# arduboy-progger.net
KiCad netlist of a schematic drawn in EAGLE
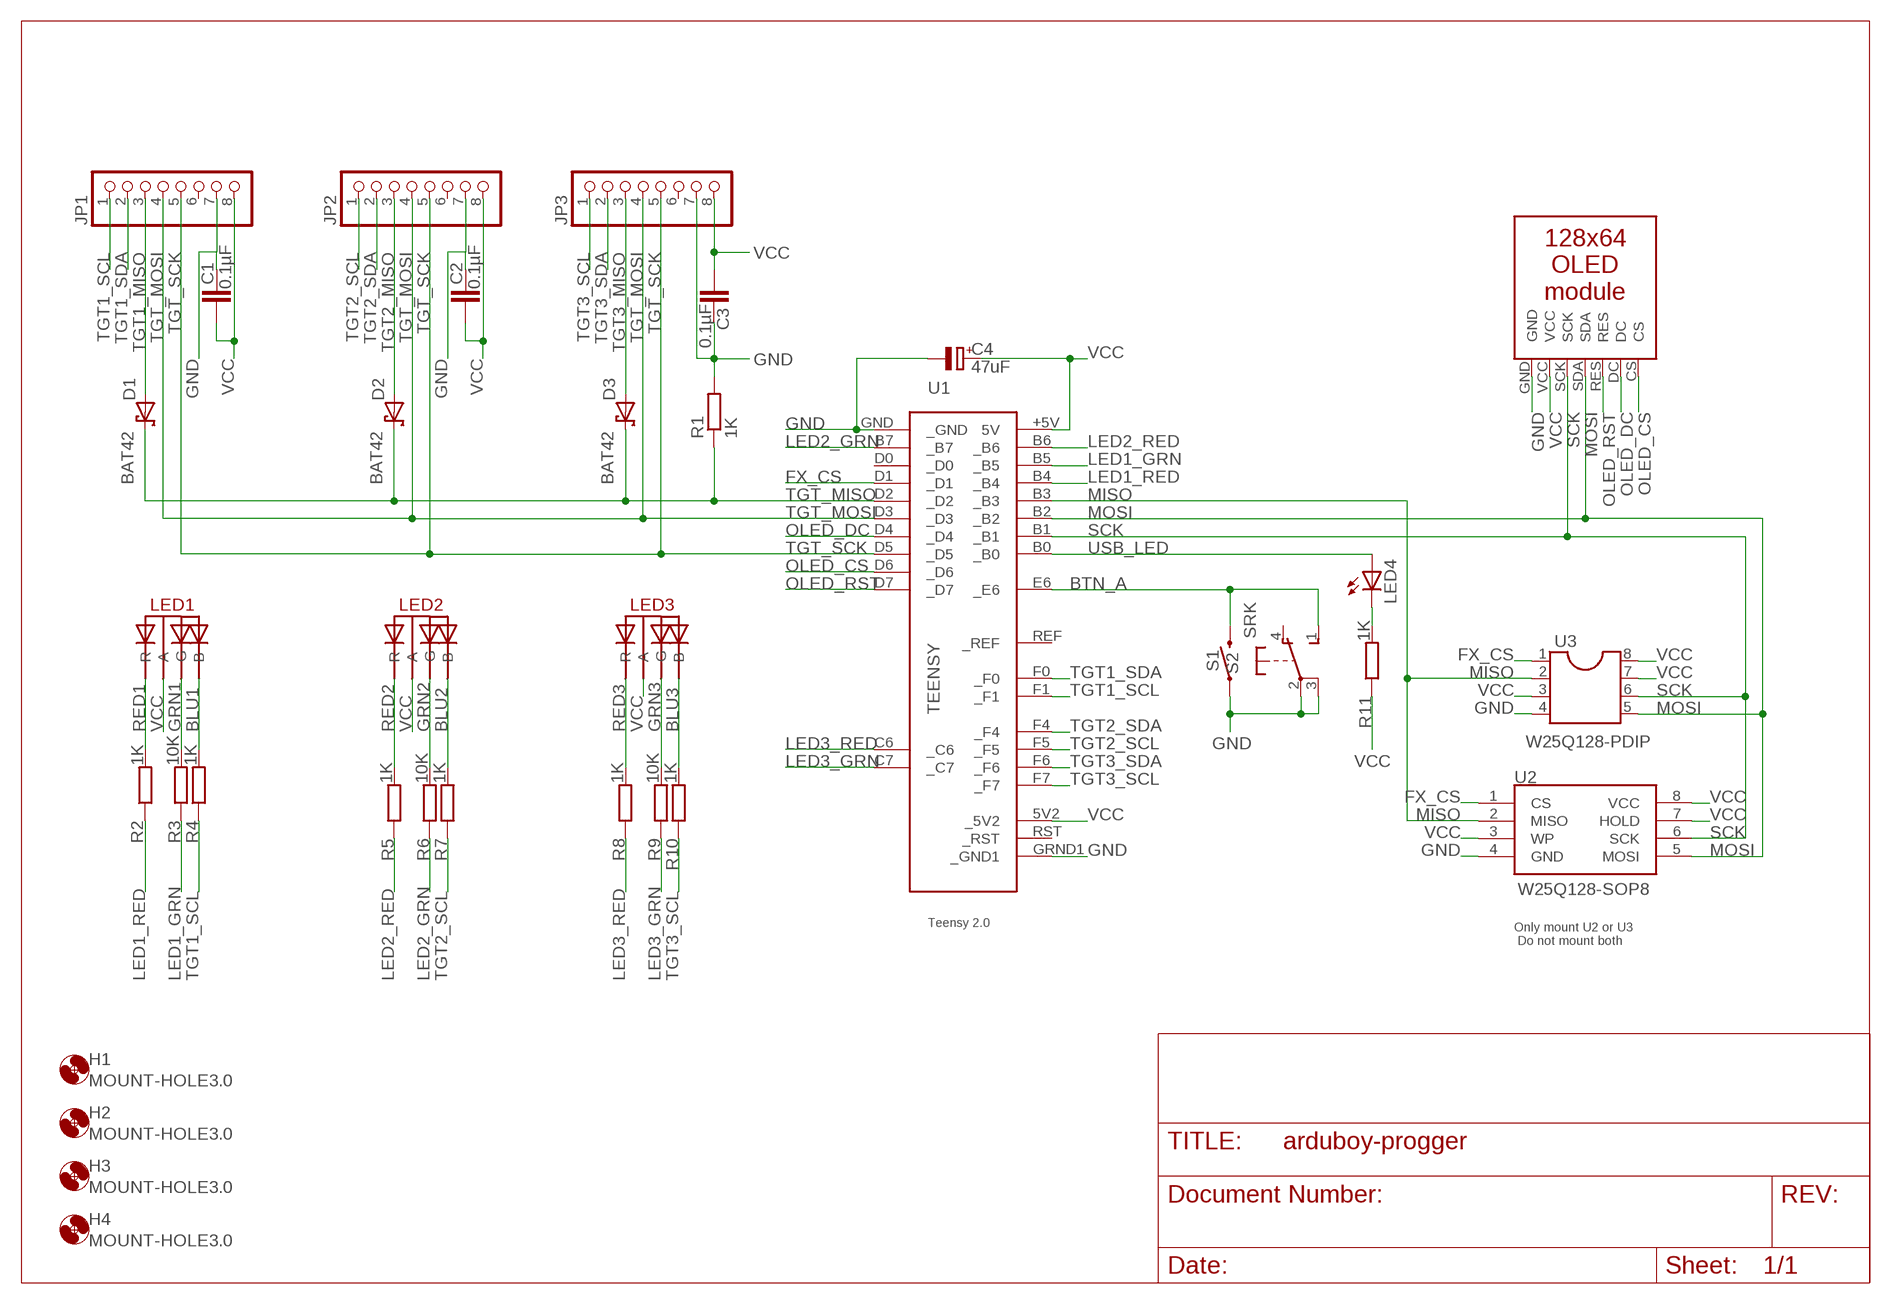
[diagram p0: schematic, sheet 1]

(export (version "E")
  (design (tool "Eeschema 10.0.6"))
  (components
    (comp (ref "C1")
      (value "0.1µF")
      (footprint "eagle-import:C025-025X050")
      (libsource (lib "eagle-import") (part "C-EU025-025X050"))
    )
    (comp (ref "C2")
      (value "0.1µF")
      (footprint "eagle-import:C025-025X050")
      (libsource (lib "eagle-import") (part "C-EU025-025X050"))
    )
    (comp (ref "C3")
      (value "0.1µF")
      (footprint "eagle-import:C025-025X050")
      (libsource (lib "eagle-import") (part "C-EU025-025X050"))
    )
    (comp (ref "C4")
      (value "47uF")
      (footprint "eagle-import:E2,5-6")
      (libsource (lib "eagle-import") (part "CPOL-EUE2.5-6"))
    )
    (comp (ref "D1")
      (value "BAT42")
      (footprint "eagle-import:DO35-10")
      (libsource (lib "eagle-import") (part "BAT42"))
    )
    (comp (ref "D2")
      (value "BAT42")
      (footprint "eagle-import:DO35-10")
      (libsource (lib "eagle-import") (part "BAT42"))
    )
    (comp (ref "D3")
      (value "BAT42")
      (footprint "eagle-import:DO35-10")
      (libsource (lib "eagle-import") (part "BAT42"))
    )
    (comp (ref "H1")
      (value "MOUNT-HOLE3.0")
      (footprint "eagle-import:3,0")
      (libsource (lib "eagle-import") (part "MOUNT-HOLE3.0"))
    )
    (comp (ref "H2")
      (value "MOUNT-HOLE3.0")
      (footprint "eagle-import:3,0")
      (libsource (lib "eagle-import") (part "MOUNT-HOLE3.0"))
    )
    (comp (ref "H3")
      (value "MOUNT-HOLE3.0")
      (footprint "eagle-import:3,0")
      (libsource (lib "eagle-import") (part "MOUNT-HOLE3.0"))
    )
    (comp (ref "H4")
      (value "MOUNT-HOLE3.0")
      (footprint "eagle-import:3,0")
      (libsource (lib "eagle-import") (part "MOUNT-HOLE3.0"))
    )
    (comp (ref "JP1")
      (value "PINHD-1X8")
      (footprint "eagle-import:1X08")
      (libsource (lib "eagle-import") (part "PINHD-1X8"))
    )
    (comp (ref "JP2")
      (value "PINHD-1X8")
      (footprint "eagle-import:1X08")
      (libsource (lib "eagle-import") (part "PINHD-1X8"))
    )
    (comp (ref "JP3")
      (value "PINHD-1X8")
      (footprint "eagle-import:1X08")
      (libsource (lib "eagle-import") (part "PINHD-1X8"))
    )
    (comp (ref "LED1")
      (value "5MMRGBLED-CA")
      (footprint "eagle-import:LED5MMRGB")
      (libsource (lib "eagle-import") (part "5MMRGBLED-CA"))
    )
    (comp (ref "LED2")
      (value "5MMRGBLED-CA")
      (footprint "eagle-import:LED5MMRGB")
      (libsource (lib "eagle-import") (part "5MMRGBLED-CA"))
    )
    (comp (ref "LED3")
      (value "5MMRGBLED-CA")
      (footprint "eagle-import:LED5MMRGB")
      (libsource (lib "eagle-import") (part "5MMRGBLED-CA"))
    )
    (comp (ref "LED4")
      (value "LED5MM")
      (footprint "eagle-import:LED5MM")
      (libsource (lib "eagle-import") (part "LED5MM"))
    )
    (comp (ref "OLED1")
      (value "OLED")
      (footprint "eagle-import:OLED")
      (libsource (lib "eagle-import") (part "OLED"))
    )
    (comp (ref "R1")
      (value "1K")
      (footprint "eagle-import:0207_10")
      (libsource (lib "eagle-import") (part "R-EU_0207/10"))
    )
    (comp (ref "R2")
      (value "1K")
      (footprint "eagle-import:0207_10")
      (libsource (lib "eagle-import") (part "R-EU_0207/10"))
    )
    (comp (ref "R3")
      (value "10K")
      (footprint "eagle-import:0207_10")
      (libsource (lib "eagle-import") (part "R-EU_0207/10"))
    )
    (comp (ref "R4")
      (value "1K")
      (footprint "eagle-import:0207_10")
      (libsource (lib "eagle-import") (part "R-EU_0207/10"))
    )
    (comp (ref "R5")
      (value "1K")
      (footprint "eagle-import:0207_10")
      (libsource (lib "eagle-import") (part "R-EU_0207/10"))
    )
    (comp (ref "R6")
      (value "10K")
      (footprint "eagle-import:0207_10")
      (libsource (lib "eagle-import") (part "R-EU_0207/10"))
    )
    (comp (ref "R7")
      (value "1K")
      (footprint "eagle-import:0207_10")
      (libsource (lib "eagle-import") (part "R-EU_0207/10"))
    )
    (comp (ref "R8")
      (value "1K")
      (footprint "eagle-import:0207_10")
      (libsource (lib "eagle-import") (part "R-EU_0207/10"))
    )
    (comp (ref "R9")
      (value "10K")
      (footprint "eagle-import:0207_10")
      (libsource (lib "eagle-import") (part "R-EU_0207/10"))
    )
    (comp (ref "R10")
      (value "1K")
      (footprint "eagle-import:0207_10")
      (libsource (lib "eagle-import") (part "R-EU_0207/10"))
    )
    (comp (ref "R11")
      (value "1K")
      (footprint "eagle-import:0207_10")
      (libsource (lib "eagle-import") (part "R-EU_0207/10"))
    )
    (comp (ref "S1")
      (value "MOMENTARY-SWITCH-SPST-PTH-6.0MM")
      (footprint "eagle-import:TACTILE_SWITCH_PTH_6.0MM")
      (libsource (lib "eagle-import") (part "MOMENTARY-SWITCH-SPST-PTH-6.0MM"))
    )
    (comp (ref "S2")
      (value "SRK")
      (footprint "eagle-import:SRK")
      (libsource (lib "eagle-import") (part "SRK"))
    )
    (comp (ref "U1")
      (value "TEENSY")
      (footprint "eagle-import:TEENSY")
      (libsource (lib "eagle-import") (part "TEENSY"))
    )
    (comp (ref "U2")
      (value "W25Q128-SOP8")
      (footprint "eagle-import:SO08-EIAJ")
      (libsource (lib "eagle-import") (part "SPI_FLASH-X25XXSMD1"))
    )
    (comp (ref "U3")
      (value "W25Q128-PDIP")
      (footprint "eagle-import:SOCKET-08")
      (libsource (lib "eagle-import") (part "DIL8S"))
    )
  )
  (nets
    (net (code "1") (name "/BLU1") (class "Default")
      (node (ref "LED1") (pin "B$1") (pinfunction "B_B$1") (pintype "bidirectional"))
      (node (ref "R4") (pin "2") (pinfunction "2_2") (pintype "passive"))
    )
    (net (code "2") (name "/BLU2") (class "Default")
      (node (ref "LED2") (pin "B$1") (pinfunction "B_B$1") (pintype "bidirectional"))
      (node (ref "R7") (pin "2") (pinfunction "2_2") (pintype "passive"))
    )
    (net (code "3") (name "/BLU3") (class "Default")
      (node (ref "LED3") (pin "B$1") (pinfunction "B_B$1") (pintype "bidirectional"))
      (node (ref "R10") (pin "2") (pinfunction "2_2") (pintype "passive"))
    )
    (net (code "4") (name "/BTN_A") (class "Default")
      (node (ref "S1") (pin "3") (pinfunction "2_3") (pintype "passive"))
      (node (ref "S2") (pin "1") (pinfunction "S_1") (pintype "passive"))
      (node (ref "U1") (pin "E6") (pinfunction "_E6_E6") (pintype "bidirectional"))
    )
    (net (code "5") (name "/FX_CS") (class "Default")
      (node (ref "U1") (pin "D1") (pinfunction "_D1_D1") (pintype "bidirectional"))
      (node (ref "U2") (pin "1") (pinfunction "CS_1") (pintype "bidirectional"))
      (node (ref "U3") (pin "1") (pinfunction "1_1") (pintype "passive"))
    )
    (net (code "6") (name "/GND") (class "Default")
      (node (ref "C1") (pin "1") (pinfunction "1_1") (pintype "passive"))
      (node (ref "C2") (pin "1") (pinfunction "1_1") (pintype "passive"))
      (node (ref "C3") (pin "1") (pinfunction "1_1") (pintype "passive"))
      (node (ref "C4") (pin "-") (pinfunction "-_-") (pintype "passive"))
      (node (ref "JP1") (pin "7") (pinfunction "7_7") (pintype "passive"))
      (node (ref "JP2") (pin "7") (pinfunction "7_7") (pintype "passive"))
      (node (ref "JP3") (pin "7") (pinfunction "7_7") (pintype "passive"))
      (node (ref "OLED1") (pin "GND") (pinfunction "GND_GND") (pintype "power_in"))
      (node (ref "R1") (pin "2") (pinfunction "2_2") (pintype "passive"))
      (node (ref "S1") (pin "1") (pinfunction "1_1") (pintype "passive"))
      (node (ref "S2") (pin "2") (pinfunction "P_2") (pintype "passive"))
      (node (ref "S2") (pin "3") (pinfunction "P_3") (pintype "passive"))
      (node (ref "U1") (pin "GND") (pinfunction "_GND_GND") (pintype "bidirectional"))
      (node (ref "U1") (pin "GRND1") (pinfunction "_GND1_GRND1") (pintype "bidirectional"))
      (node (ref "U2") (pin "4") (pinfunction "GND_4") (pintype "power_in"))
      (node (ref "U3") (pin "4") (pinfunction "4_4") (pintype "passive"))
    )
    (net (code "7") (name "/GRN1") (class "Default")
      (node (ref "LED1") (pin "G$1") (pinfunction "G_G$1") (pintype "bidirectional"))
      (node (ref "R3") (pin "2") (pinfunction "2_2") (pintype "passive"))
    )
    (net (code "8") (name "/GRN2") (class "Default")
      (node (ref "LED2") (pin "G$1") (pinfunction "G_G$1") (pintype "bidirectional"))
      (node (ref "R6") (pin "2") (pinfunction "2_2") (pintype "passive"))
    )
    (net (code "9") (name "/GRN3") (class "Default")
      (node (ref "LED3") (pin "G$1") (pinfunction "G_G$1") (pintype "bidirectional"))
      (node (ref "R9") (pin "2") (pinfunction "2_2") (pintype "passive"))
    )
    (net (code "10") (name "/LED1_GRN") (class "Default")
      (node (ref "R3") (pin "1") (pinfunction "1_1") (pintype "passive"))
      (node (ref "U1") (pin "B5") (pinfunction "_B5_B5") (pintype "bidirectional"))
    )
    (net (code "11") (name "/LED1_RED") (class "Default")
      (node (ref "R2") (pin "1") (pinfunction "1_1") (pintype "passive"))
      (node (ref "U1") (pin "B4") (pinfunction "_B4_B4") (pintype "bidirectional"))
    )
    (net (code "12") (name "/LED2_GRN") (class "Default")
      (node (ref "R6") (pin "1") (pinfunction "1_1") (pintype "passive"))
      (node (ref "U1") (pin "B7") (pinfunction "_B7_B7") (pintype "bidirectional"))
    )
    (net (code "13") (name "/LED2_RED") (class "Default")
      (node (ref "R5") (pin "1") (pinfunction "1_1") (pintype "passive"))
      (node (ref "U1") (pin "B6") (pinfunction "_B6_B6") (pintype "bidirectional"))
    )
    (net (code "14") (name "/LED3_GRN") (class "Default")
      (node (ref "R9") (pin "1") (pinfunction "1_1") (pintype "passive"))
      (node (ref "U1") (pin "C7") (pinfunction "_C7_C7") (pintype "bidirectional"))
    )
    (net (code "15") (name "/LED3_RED") (class "Default")
      (node (ref "R8") (pin "1") (pinfunction "1_1") (pintype "passive"))
      (node (ref "U1") (pin "C6") (pinfunction "_C6_C6") (pintype "bidirectional"))
    )
    (net (code "16") (name "/MISO") (class "Default")
      (node (ref "U1") (pin "B3") (pinfunction "_B3_B3") (pintype "bidirectional"))
      (node (ref "U2") (pin "2") (pinfunction "MISO_2") (pintype "bidirectional"))
      (node (ref "U3") (pin "2") (pinfunction "2_2") (pintype "passive"))
    )
    (net (code "17") (name "/MOSI") (class "Default")
      (node (ref "OLED1") (pin "SDA") (pinfunction "SDA_SDA") (pintype "input"))
      (node (ref "U1") (pin "B2") (pinfunction "_B2_B2") (pintype "bidirectional"))
      (node (ref "U2") (pin "5") (pinfunction "MOSI_5") (pintype "bidirectional"))
      (node (ref "U3") (pin "5") (pinfunction "5_5") (pintype "passive"))
    )
    (net (code "18") (name "/OLED_CS") (class "Default")
      (node (ref "OLED1") (pin "CS") (pinfunction "CS_CS") (pintype "input"))
      (node (ref "U1") (pin "D6") (pinfunction "_D6_D6") (pintype "bidirectional"))
    )
    (net (code "19") (name "/OLED_DC") (class "Default")
      (node (ref "OLED1") (pin "DC") (pinfunction "DC_DC") (pintype "input"))
      (node (ref "U1") (pin "D4") (pinfunction "_D4_D4") (pintype "bidirectional"))
    )
    (net (code "20") (name "/OLED_RST") (class "Default")
      (node (ref "OLED1") (pin "RES") (pinfunction "RES_RES") (pintype "input"))
      (node (ref "U1") (pin "D7") (pinfunction "_D7_D7") (pintype "bidirectional"))
    )
    (net (code "21") (name "/RED1") (class "Default")
      (node (ref "LED1") (pin "R$1") (pinfunction "R_R$1") (pintype "bidirectional"))
      (node (ref "R2") (pin "2") (pinfunction "2_2") (pintype "passive"))
    )
    (net (code "22") (name "/RED2") (class "Default")
      (node (ref "LED2") (pin "R$1") (pinfunction "R_R$1") (pintype "bidirectional"))
      (node (ref "R5") (pin "2") (pinfunction "2_2") (pintype "passive"))
    )
    (net (code "23") (name "/RED3") (class "Default")
      (node (ref "LED3") (pin "R$1") (pinfunction "R_R$1") (pintype "bidirectional"))
      (node (ref "R8") (pin "2") (pinfunction "2_2") (pintype "passive"))
    )
    (net (code "24") (name "/SCK") (class "Default")
      (node (ref "OLED1") (pin "SCK") (pinfunction "SCK_SCK") (pintype "input"))
      (node (ref "U1") (pin "B1") (pinfunction "_B1_B1") (pintype "bidirectional"))
      (node (ref "U2") (pin "6") (pinfunction "SCK_6") (pintype "bidirectional"))
      (node (ref "U3") (pin "6") (pinfunction "6_6") (pintype "passive"))
    )
    (net (code "25") (name "/TGT1_MISO") (class "Default")
      (node (ref "D1") (pin "A") (pinfunction "A_A") (pintype "passive"))
      (node (ref "JP1") (pin "3") (pinfunction "3_3") (pintype "passive"))
    )
    (net (code "26") (name "/TGT1_SCL") (class "Default")
      (node (ref "JP1") (pin "1") (pinfunction "1_1") (pintype "passive"))
      (node (ref "R4") (pin "1") (pinfunction "1_1") (pintype "passive"))
      (node (ref "U1") (pin "F1") (pinfunction "_F1_F1") (pintype "bidirectional"))
    )
    (net (code "27") (name "/TGT1_SDA") (class "Default")
      (node (ref "JP1") (pin "2") (pinfunction "2_2") (pintype "passive"))
      (node (ref "U1") (pin "F0") (pinfunction "_F0_F0") (pintype "bidirectional"))
    )
    (net (code "28") (name "/TGT2_MISO") (class "Default")
      (node (ref "D2") (pin "A") (pinfunction "A_A") (pintype "passive"))
      (node (ref "JP2") (pin "3") (pinfunction "3_3") (pintype "passive"))
    )
    (net (code "29") (name "/TGT2_SCL") (class "Default")
      (node (ref "JP2") (pin "1") (pinfunction "1_1") (pintype "passive"))
      (node (ref "R7") (pin "1") (pinfunction "1_1") (pintype "passive"))
      (node (ref "U1") (pin "F5") (pinfunction "_F5_F5") (pintype "bidirectional"))
    )
    (net (code "30") (name "/TGT2_SDA") (class "Default")
      (node (ref "JP2") (pin "2") (pinfunction "2_2") (pintype "passive"))
      (node (ref "U1") (pin "F4") (pinfunction "_F4_F4") (pintype "bidirectional"))
    )
    (net (code "31") (name "/TGT3_MISO") (class "Default")
      (node (ref "D3") (pin "A") (pinfunction "A_A") (pintype "passive"))
      (node (ref "JP3") (pin "3") (pinfunction "3_3") (pintype "passive"))
    )
    (net (code "32") (name "/TGT3_SCL") (class "Default")
      (node (ref "JP3") (pin "1") (pinfunction "1_1") (pintype "passive"))
      (node (ref "R10") (pin "1") (pinfunction "1_1") (pintype "passive"))
      (node (ref "U1") (pin "F7") (pinfunction "_F7_F7") (pintype "bidirectional"))
    )
    (net (code "33") (name "/TGT3_SDA") (class "Default")
      (node (ref "JP3") (pin "2") (pinfunction "2_2") (pintype "passive"))
      (node (ref "U1") (pin "F6") (pinfunction "_F6_F6") (pintype "bidirectional"))
    )
    (net (code "34") (name "/TGT_MISO") (class "Default")
      (node (ref "D1") (pin "C") (pinfunction "C_C") (pintype "passive"))
      (node (ref "D2") (pin "C") (pinfunction "C_C") (pintype "passive"))
      (node (ref "D3") (pin "C") (pinfunction "C_C") (pintype "passive"))
      (node (ref "R1") (pin "1") (pinfunction "1_1") (pintype "passive"))
      (node (ref "U1") (pin "D2") (pinfunction "_D2_D2") (pintype "bidirectional"))
    )
    (net (code "35") (name "/TGT_MOSI") (class "Default")
      (node (ref "JP1") (pin "4") (pinfunction "4_4") (pintype "passive"))
      (node (ref "JP2") (pin "4") (pinfunction "4_4") (pintype "passive"))
      (node (ref "JP3") (pin "4") (pinfunction "4_4") (pintype "passive"))
      (node (ref "U1") (pin "D3") (pinfunction "_D3_D3") (pintype "bidirectional"))
    )
    (net (code "36") (name "/TGT_SCK") (class "Default")
      (node (ref "JP1") (pin "5") (pinfunction "5_5") (pintype "passive"))
      (node (ref "JP2") (pin "5") (pinfunction "5_5") (pintype "passive"))
      (node (ref "JP3") (pin "5") (pinfunction "5_5") (pintype "passive"))
      (node (ref "U1") (pin "D5") (pinfunction "_D5_D5") (pintype "bidirectional"))
    )
    (net (code "37") (name "/USB_LED") (class "Default")
      (node (ref "LED4") (pin "A") (pinfunction "A_A") (pintype "passive"))
      (node (ref "U1") (pin "B0") (pinfunction "_B0_B0") (pintype "bidirectional"))
    )
    (net (code "38") (name "/VCC") (class "Default")
      (node (ref "C1") (pin "2") (pinfunction "2_2") (pintype "passive"))
      (node (ref "C2") (pin "2") (pinfunction "2_2") (pintype "passive"))
      (node (ref "C3") (pin "2") (pinfunction "2_2") (pintype "passive"))
      (node (ref "C4") (pin "+") (pinfunction "+_+") (pintype "passive"))
      (node (ref "JP1") (pin "8") (pinfunction "8_8") (pintype "passive"))
      (node (ref "JP2") (pin "8") (pinfunction "8_8") (pintype "passive"))
      (node (ref "JP3") (pin "8") (pinfunction "8_8") (pintype "passive"))
      (node (ref "LED1") (pin "C$1") (pinfunction "A_C$1") (pintype "bidirectional"))
      (node (ref "LED2") (pin "C$1") (pinfunction "A_C$1") (pintype "bidirectional"))
      (node (ref "LED3") (pin "C$1") (pinfunction "A_C$1") (pintype "bidirectional"))
      (node (ref "OLED1") (pin "VCC") (pinfunction "VCC_VCC") (pintype "power_in"))
      (node (ref "R11") (pin "1") (pinfunction "1_1") (pintype "passive"))
      (node (ref "U1") (pin "+5V") (pinfunction "5V_+5V") (pintype "bidirectional"))
      (node (ref "U1") (pin "5V2") (pinfunction "_5V2_5V2") (pintype "bidirectional"))
      (node (ref "U2") (pin "3") (pinfunction "WP_3") (pintype "bidirectional"))
      (node (ref "U2") (pin "7") (pinfunction "HOLD_7") (pintype "bidirectional"))
      (node (ref "U2") (pin "8") (pinfunction "VCC_8") (pintype "power_in"))
      (node (ref "U3") (pin "3") (pinfunction "3_3") (pintype "passive"))
      (node (ref "U3") (pin "7") (pinfunction "7_7") (pintype "passive"))
      (node (ref "U3") (pin "8") (pinfunction "8_8") (pintype "passive"))
    )
    (net (code "39") (name "Net-(LED4-C)") (class "Default")
      (node (ref "LED4") (pin "K") (pinfunction "C_K") (pintype "passive"))
      (node (ref "R11") (pin "2") (pinfunction "2_2") (pintype "passive"))
    )
    (net (code "40") (name "unconnected-(JP1-Pad6)") (class "Default")
      (node (ref "JP1") (pin "6") (pinfunction "6_6") (pintype "passive"))
    )
    (net (code "41") (name "unconnected-(JP2-Pad6)") (class "Default")
      (node (ref "JP2") (pin "6") (pinfunction "6_6") (pintype "passive"))
    )
    (net (code "42") (name "unconnected-(JP3-Pad6)") (class "Default")
      (node (ref "JP3") (pin "6") (pinfunction "6_6") (pintype "passive"))
    )
    (net (code "43") (name "unconnected-(S2-O-Pad4)") (class "Default")
      (node (ref "S2") (pin "4") (pinfunction "O_4") (pintype "passive"))
    )
    (net (code "44") (name "unconnected-(U1-_D0-PadD0)") (class "Default")
      (node (ref "U1") (pin "D0") (pinfunction "_D0_D0") (pintype "bidirectional"))
    )
    (net (code "45") (name "unconnected-(U1-_REF-PadREF)") (class "Default")
      (node (ref "U1") (pin "REF") (pinfunction "_REF_REF") (pintype "bidirectional"))
    )
    (net (code "46") (name "unconnected-(U1-_RST-PadRST)") (class "Default")
      (node (ref "U1") (pin "RST") (pinfunction "_RST_RST") (pintype "bidirectional"))
    )
  )
)
